# PCB_Design.net
KiCad netlist of a schematic drawn in EAGLE
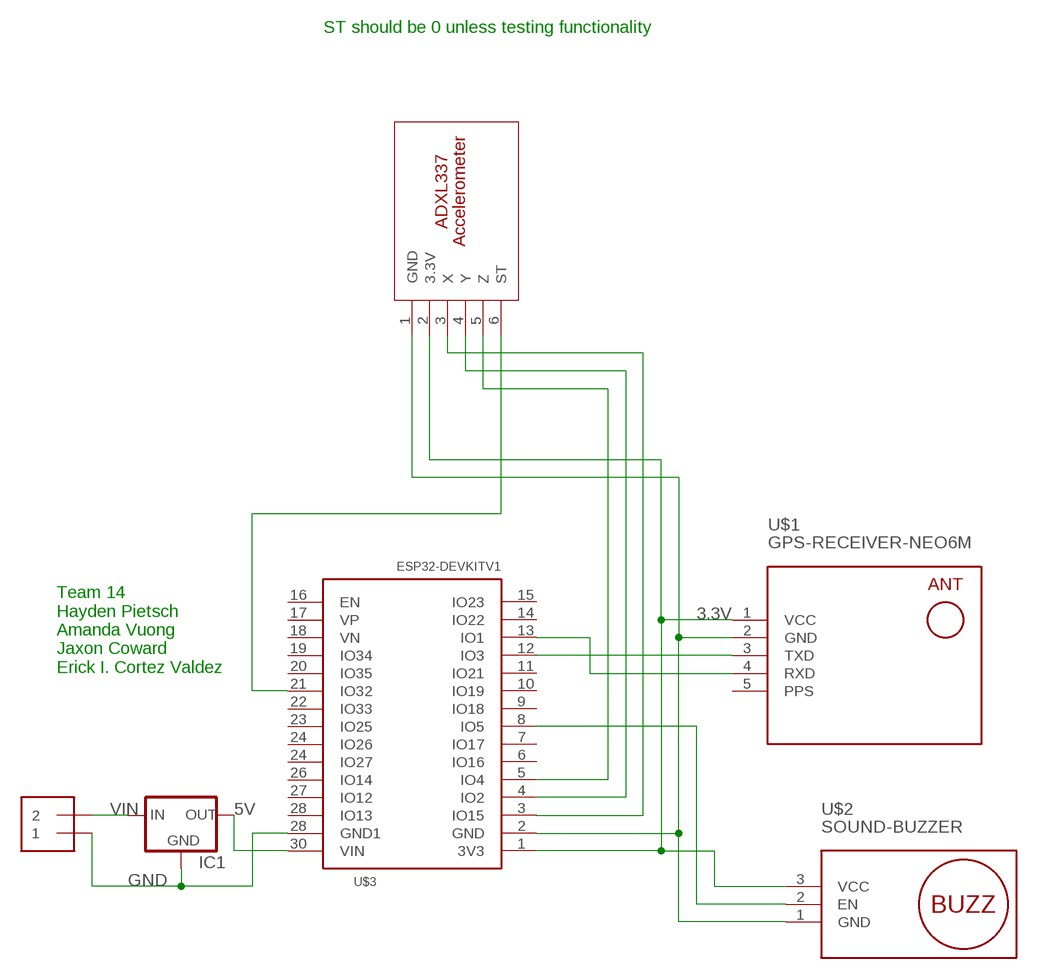
[diagram p0: schematic, sheet 1]

(export (version "E")
  (design (tool "Eeschema 10.0.6"))
  (components
    (comp (ref "IC1")
      (value "V_REG_78XXSIDE")
      (footprint "eagle-import:78XXL")
      (fields (field (name "MF") "STMICROELECTRONICS") (field (name "MPN") "L7805ABV"))
      (libsource (lib "eagle-import") (part "V_REG_78XXSIDE"))
    )
    (comp (ref "J1")
      (value "1X2-3.5MM")
      (footprint "eagle-import:1X2-3.5MM")
      (libsource (lib "eagle-import") (part "1X2-3.5MM"))
    )
    (comp (ref "U$1")
      (value "GPS-RECEIVER-NEO6M")
      (footprint "eagle-import:GPS-RECEIVER-NEO6M")
      (fields (field (name "MF") "NEOHM - TE CONNECTIVITY") (field (name "MPN") "YR1B909KCC"))
      (libsource (lib "eagle-import") (part "GPS-RECEIVER-NEO6M"))
    )
    (comp (ref "U$2")
      (value "SOUND-BUZZER")
      (footprint "eagle-import:SOUND-BUZZER")
      (libsource (lib "eagle-import") (part "SOUND-BUZZER"))
    )
    (comp (ref "U$3")
      (value "ESP32DEVKITV1")
      (footprint "eagle-import:ESP32-DEVKITV1")
      (libsource (lib "eagle-import") (part "ESP32DEVKITV1"))
    )
    (comp (ref "U$4")
      (value "ADXL337_ACCELEROMETER")
      (footprint "eagle-import:ADXL337BREAKOUT")
      (libsource (lib "eagle-import") (part "ADXL337_ACCELEROMETER"))
    )
  )
  (nets
    (net (code "1") (name "/3.3V") (class "Default")
      (node (ref "U$1") (pin "1") (pinfunction "VCC_1") (pintype "bidirectional"))
      (node (ref "U$2") (pin "3") (pinfunction "VCC_3") (pintype "power_in"))
      (node (ref "U$3") (pin "1") (pinfunction "3V3_1") (pintype "bidirectional"))
      (node (ref "U$4") (pin "2") (pinfunction "3.3V_2") (pintype "bidirectional"))
    )
    (net (code "2") (name "/5V") (class "Default")
      (node (ref "IC1") (pin "OUT") (pinfunction "OUT_OUT") (pintype "output"))
      (node (ref "U$3") (pin "30") (pinfunction "VIN_30") (pintype "bidirectional"))
    )
    (net (code "3") (name "/GND") (class "Default")
      (node (ref "IC1") (pin "GND") (pinfunction "GND_GND") (pintype "input"))
      (node (ref "J1") (pin "1") (pinfunction "1_1") (pintype "passive"))
      (node (ref "U$1") (pin "2") (pinfunction "GND_2") (pintype "bidirectional"))
      (node (ref "U$2") (pin "1") (pinfunction "GND_1") (pintype "power_in"))
      (node (ref "U$3") (pin "2") (pinfunction "GND_2") (pintype "bidirectional"))
      (node (ref "U$3") (pin "28") (pinfunction "GND1_28") (pintype "bidirectional"))
      (node (ref "U$4") (pin "1") (pinfunction "GND_1") (pintype "bidirectional"))
    )
    (net (code "4") (name "/PPS") (class "Default")
      (node (ref "U$1") (pin "5") (pinfunction "PPS_5") (pintype "power_in"))
    )
    (net (code "5") (name "/VIN") (class "Default")
      (node (ref "IC1") (pin "IN") (pinfunction "IN_IN") (pintype "input"))
      (node (ref "J1") (pin "2") (pinfunction "2_2") (pintype "passive"))
    )
    (net (code "6") (name "Net-(U$1-RXD)") (class "Default")
      (node (ref "U$1") (pin "4") (pinfunction "RXD_4") (pintype "power_in"))
      (node (ref "U$3") (pin "13") (pinfunction "IO1_13") (pintype "bidirectional"))
    )
    (net (code "7") (name "Net-(U$1-TXD)") (class "Default")
      (node (ref "U$1") (pin "3") (pinfunction "TXD_3") (pintype "bidirectional"))
      (node (ref "U$3") (pin "12") (pinfunction "IO3_12") (pintype "bidirectional"))
    )
    (net (code "8") (name "Net-(U$2-EN)") (class "Default")
      (node (ref "U$2") (pin "2") (pinfunction "EN_2") (pintype "input"))
      (node (ref "U$3") (pin "8") (pinfunction "IO5_8") (pintype "bidirectional"))
    )
    (net (code "9") (name "Net-(U$3-IO2)") (class "Default")
      (node (ref "U$3") (pin "4") (pinfunction "IO2_4") (pintype "bidirectional"))
      (node (ref "U$4") (pin "4") (pinfunction "Y_4") (pintype "bidirectional"))
    )
    (net (code "10") (name "Net-(U$3-IO4)") (class "Default")
      (node (ref "U$3") (pin "5") (pinfunction "IO4_5") (pintype "bidirectional"))
      (node (ref "U$4") (pin "5") (pinfunction "Z_5") (pintype "bidirectional"))
    )
    (net (code "11") (name "Net-(U$3-IO15)") (class "Default")
      (node (ref "U$3") (pin "3") (pinfunction "IO15_3") (pintype "bidirectional"))
      (node (ref "U$4") (pin "3") (pinfunction "X_3") (pintype "bidirectional"))
    )
    (net (code "12") (name "Net-(U$3-IO32)") (class "Default")
      (node (ref "U$3") (pin "21") (pinfunction "IO32_21") (pintype "bidirectional"))
      (node (ref "U$4") (pin "6") (pinfunction "ST_6") (pintype "bidirectional"))
    )
    (net (code "13") (name "unconnected-(U$3-EN-Pad16)") (class "Default")
      (node (ref "U$3") (pin "16") (pinfunction "EN_16") (pintype "bidirectional"))
    )
    (net (code "14") (name "unconnected-(U$3-IO12-Pad27)") (class "Default")
      (node (ref "U$3") (pin "27") (pinfunction "IO12_27") (pintype "bidirectional"))
    )
    (net (code "15") (name "unconnected-(U$3-IO13-Pad28)") (class "Default")
      (node (ref "U$3") (pin "28") (pinfunction "IO13_28") (pintype "bidirectional"))
    )
    (net (code "16") (name "unconnected-(U$3-IO14-Pad26)") (class "Default")
      (node (ref "U$3") (pin "26") (pinfunction "IO14_26") (pintype "bidirectional"))
    )
    (net (code "17") (name "unconnected-(U$3-IO16-Pad6)") (class "Default")
      (node (ref "U$3") (pin "6") (pinfunction "IO16_6") (pintype "bidirectional"))
    )
    (net (code "18") (name "unconnected-(U$3-IO17-Pad7)") (class "Default")
      (node (ref "U$3") (pin "7") (pinfunction "IO17_7") (pintype "bidirectional"))
    )
    (net (code "19") (name "unconnected-(U$3-IO18-Pad9)") (class "Default")
      (node (ref "U$3") (pin "9") (pinfunction "IO18_9") (pintype "bidirectional"))
    )
    (net (code "20") (name "unconnected-(U$3-IO19-Pad10)") (class "Default")
      (node (ref "U$3") (pin "10") (pinfunction "IO19_10") (pintype "bidirectional"))
    )
    (net (code "21") (name "unconnected-(U$3-IO21-Pad11)") (class "Default")
      (node (ref "U$3") (pin "11") (pinfunction "IO21_11") (pintype "bidirectional"))
    )
    (net (code "22") (name "unconnected-(U$3-IO22-Pad14)") (class "Default")
      (node (ref "U$3") (pin "14") (pinfunction "IO22_14") (pintype "bidirectional"))
    )
    (net (code "23") (name "unconnected-(U$3-IO23-Pad15)") (class "Default")
      (node (ref "U$3") (pin "15") (pinfunction "IO23_15") (pintype "bidirectional"))
    )
    (net (code "24") (name "unconnected-(U$3-IO25-Pad23)") (class "Default")
      (node (ref "U$3") (pin "23") (pinfunction "IO25_23") (pintype "bidirectional"))
    )
    (net (code "25") (name "unconnected-(U$3-IO26-Pad24)") (class "Default")
      (node (ref "U$3") (pin "24") (pinfunction "IO26_24") (pintype "bidirectional"))
    )
    (net (code "26") (name "unconnected-(U$3-IO27-Pad24)") (class "Default")
      (node (ref "U$3") (pin "24") (pinfunction "IO27_24") (pintype "bidirectional"))
    )
    (net (code "27") (name "unconnected-(U$3-IO33-Pad22)") (class "Default")
      (node (ref "U$3") (pin "22") (pinfunction "IO33_22") (pintype "bidirectional"))
    )
    (net (code "28") (name "unconnected-(U$3-IO34-Pad19)") (class "Default")
      (node (ref "U$3") (pin "19") (pinfunction "IO34_19") (pintype "bidirectional"))
    )
    (net (code "29") (name "unconnected-(U$3-IO35-Pad20)") (class "Default")
      (node (ref "U$3") (pin "20") (pinfunction "IO35_20") (pintype "bidirectional"))
    )
    (net (code "30") (name "unconnected-(U$3-VN-Pad18)") (class "Default")
      (node (ref "U$3") (pin "18") (pinfunction "VN_18") (pintype "bidirectional"))
    )
    (net (code "31") (name "unconnected-(U$3-VP-Pad17)") (class "Default")
      (node (ref "U$3") (pin "17") (pinfunction "VP_17") (pintype "bidirectional"))
    )
  )
)
